# eksos-rj45-breakout-for_slot.net
KiCad netlist of a schematic drawn in EAGLE
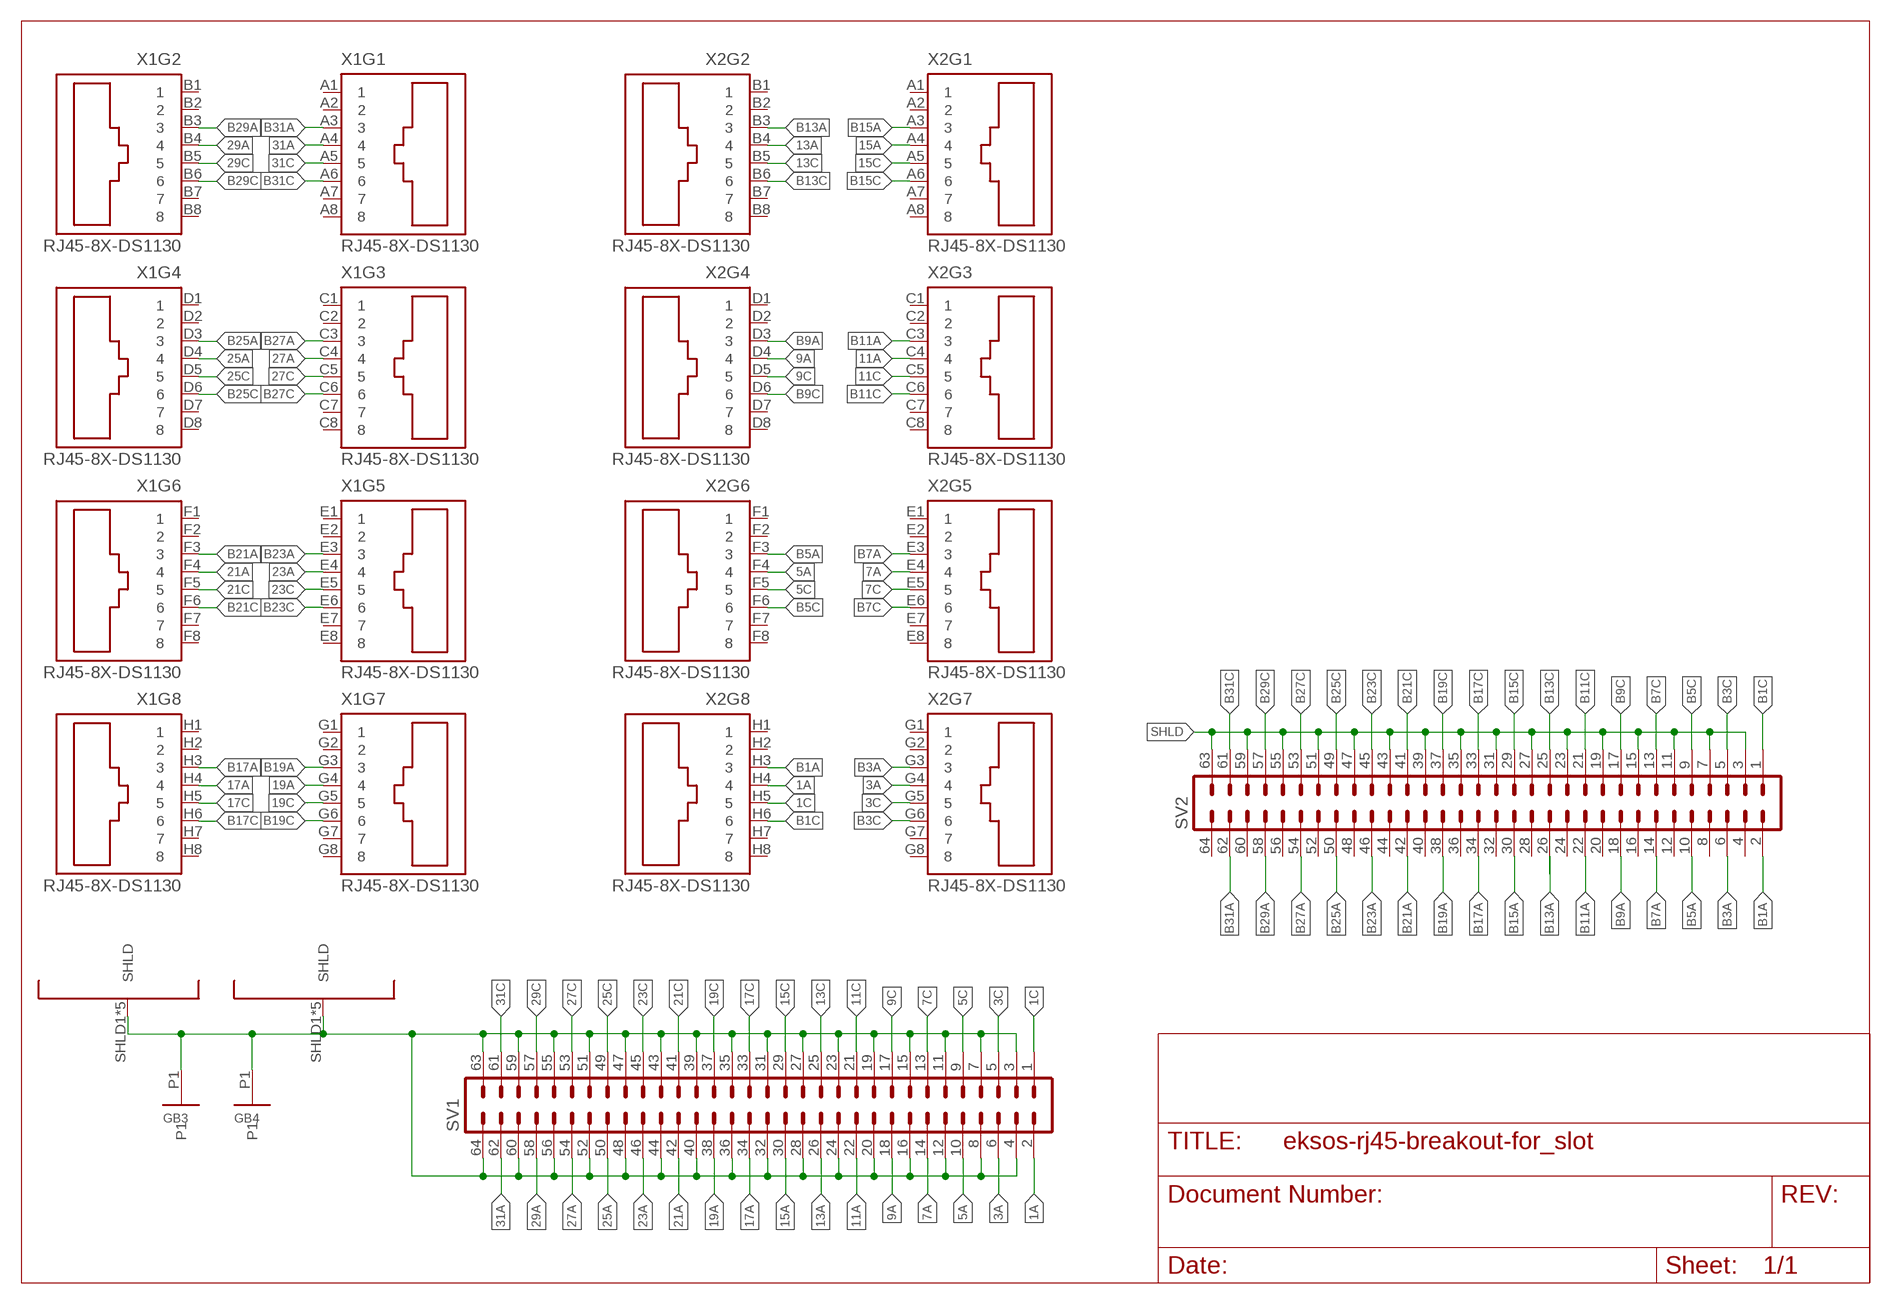
[diagram p0: schematic, sheet 1]

(export (version "E")
  (design (tool "Eeschema 10.0.6"))
  (components
    (comp (ref "GB3")
      (value "GEWINDEBLOCK-6X6X12M3")
      (footprint "eagle-import:GB6X6X12_VIA")
      (libsource (lib "eagle-import") (part "GEWINDEBLOCK-6X6X12M3"))
    )
    (comp (ref "GB4")
      (value "GEWINDEBLOCK-6X6X12M3")
      (footprint "eagle-import:GB6X6X12_VIA")
      (libsource (lib "eagle-import") (part "GEWINDEBLOCK-6X6X12M3"))
    )
    (comp (ref "SV1")
      (value "ML64")
      (footprint "eagle-import:ML64")
      (libsource (lib "eagle-import") (part "ML64"))
    )
    (comp (ref "SV2")
      (value "ML64")
      (footprint "eagle-import:ML64")
      (libsource (lib "eagle-import") (part "ML64"))
    )
    (comp (ref "X1")
      (value "RJ45-8X-DS1130")
      (footprint "eagle-import:DS1130")
      (libsource (lib "eagle-import") (part "RJ45-8X-DS1130"))
    )
    (comp (ref "X2")
      (value "RJ45-8X-DS1130")
      (footprint "eagle-import:DS1130")
      (libsource (lib "eagle-import") (part "RJ45-8X-DS1130"))
    )
  )
  (nets
    (net (code "1") (name "1A") (class "Default")
      (node (ref "SV1") (pin "2") (pinfunction "2_2") (pintype "passive"))
      (node (ref "X2") (pin "H4") (pinfunction "4_H4") (pintype "passive"))
    )
    (net (code "2") (name "1C") (class "Default")
      (node (ref "SV1") (pin "1") (pinfunction "1_1") (pintype "passive"))
      (node (ref "X2") (pin "H5") (pinfunction "5_H5") (pintype "passive"))
    )
    (net (code "3") (name "3A") (class "Default")
      (node (ref "SV1") (pin "6") (pinfunction "6_6") (pintype "passive"))
      (node (ref "X2") (pin "G4") (pinfunction "4_G4") (pintype "passive"))
    )
    (net (code "4") (name "3C") (class "Default")
      (node (ref "SV1") (pin "5") (pinfunction "5_5") (pintype "passive"))
      (node (ref "X2") (pin "G5") (pinfunction "5_G5") (pintype "passive"))
    )
    (net (code "5") (name "5A") (class "Default")
      (node (ref "SV1") (pin "10") (pinfunction "10_10") (pintype "passive"))
      (node (ref "X2") (pin "F4") (pinfunction "4_F4") (pintype "passive"))
    )
    (net (code "6") (name "5C") (class "Default")
      (node (ref "SV1") (pin "9") (pinfunction "9_9") (pintype "passive"))
      (node (ref "X2") (pin "F5") (pinfunction "5_F5") (pintype "passive"))
    )
    (net (code "7") (name "7A") (class "Default")
      (node (ref "SV1") (pin "14") (pinfunction "14_14") (pintype "passive"))
      (node (ref "X2") (pin "E4") (pinfunction "4_E4") (pintype "passive"))
    )
    (net (code "8") (name "7C") (class "Default")
      (node (ref "SV1") (pin "13") (pinfunction "13_13") (pintype "passive"))
      (node (ref "X2") (pin "E5") (pinfunction "5_E5") (pintype "passive"))
    )
    (net (code "9") (name "9A") (class "Default")
      (node (ref "SV1") (pin "18") (pinfunction "18_18") (pintype "passive"))
      (node (ref "X2") (pin "D4") (pinfunction "4_D4") (pintype "passive"))
    )
    (net (code "10") (name "9C") (class "Default")
      (node (ref "SV1") (pin "17") (pinfunction "17_17") (pintype "passive"))
      (node (ref "X2") (pin "D5") (pinfunction "5_D5") (pintype "passive"))
    )
    (net (code "11") (name "11A") (class "Default")
      (node (ref "SV1") (pin "22") (pinfunction "22_22") (pintype "passive"))
      (node (ref "X2") (pin "C4") (pinfunction "4_C4") (pintype "passive"))
    )
    (net (code "12") (name "11C") (class "Default")
      (node (ref "SV1") (pin "21") (pinfunction "21_21") (pintype "passive"))
      (node (ref "X2") (pin "C5") (pinfunction "5_C5") (pintype "passive"))
    )
    (net (code "13") (name "13A") (class "Default")
      (node (ref "SV1") (pin "26") (pinfunction "26_26") (pintype "passive"))
      (node (ref "X2") (pin "B4") (pinfunction "4_B4") (pintype "passive"))
    )
    (net (code "14") (name "13C") (class "Default")
      (node (ref "SV1") (pin "25") (pinfunction "25_25") (pintype "passive"))
      (node (ref "X2") (pin "B5") (pinfunction "5_B5") (pintype "passive"))
    )
    (net (code "15") (name "15A") (class "Default")
      (node (ref "SV1") (pin "30") (pinfunction "30_30") (pintype "passive"))
      (node (ref "X2") (pin "A4") (pinfunction "4_A4") (pintype "passive"))
    )
    (net (code "16") (name "15C") (class "Default")
      (node (ref "SV1") (pin "29") (pinfunction "29_29") (pintype "passive"))
      (node (ref "X2") (pin "A5") (pinfunction "5_A5") (pintype "passive"))
    )
    (net (code "17") (name "17A") (class "Default")
      (node (ref "SV1") (pin "34") (pinfunction "34_34") (pintype "passive"))
      (node (ref "X1") (pin "H4") (pinfunction "4_H4") (pintype "passive"))
    )
    (net (code "18") (name "17C") (class "Default")
      (node (ref "SV1") (pin "33") (pinfunction "33_33") (pintype "passive"))
      (node (ref "X1") (pin "H5") (pinfunction "5_H5") (pintype "passive"))
    )
    (net (code "19") (name "19A") (class "Default")
      (node (ref "SV1") (pin "38") (pinfunction "38_38") (pintype "passive"))
      (node (ref "X1") (pin "G4") (pinfunction "4_G4") (pintype "passive"))
    )
    (net (code "20") (name "19C") (class "Default")
      (node (ref "SV1") (pin "37") (pinfunction "37_37") (pintype "passive"))
      (node (ref "X1") (pin "G5") (pinfunction "5_G5") (pintype "passive"))
    )
    (net (code "21") (name "21A") (class "Default")
      (node (ref "SV1") (pin "42") (pinfunction "42_42") (pintype "passive"))
      (node (ref "X1") (pin "F4") (pinfunction "4_F4") (pintype "passive"))
    )
    (net (code "22") (name "21C") (class "Default")
      (node (ref "SV1") (pin "41") (pinfunction "41_41") (pintype "passive"))
      (node (ref "X1") (pin "F5") (pinfunction "5_F5") (pintype "passive"))
    )
    (net (code "23") (name "23A") (class "Default")
      (node (ref "SV1") (pin "46") (pinfunction "46_46") (pintype "passive"))
      (node (ref "X1") (pin "E4") (pinfunction "4_E4") (pintype "passive"))
    )
    (net (code "24") (name "23C") (class "Default")
      (node (ref "SV1") (pin "45") (pinfunction "45_45") (pintype "passive"))
      (node (ref "X1") (pin "E5") (pinfunction "5_E5") (pintype "passive"))
    )
    (net (code "25") (name "25A") (class "Default")
      (node (ref "SV1") (pin "50") (pinfunction "50_50") (pintype "passive"))
      (node (ref "X1") (pin "D4") (pinfunction "4_D4") (pintype "passive"))
    )
    (net (code "26") (name "25C") (class "Default")
      (node (ref "SV1") (pin "49") (pinfunction "49_49") (pintype "passive"))
      (node (ref "X1") (pin "D5") (pinfunction "5_D5") (pintype "passive"))
    )
    (net (code "27") (name "27A") (class "Default")
      (node (ref "SV1") (pin "54") (pinfunction "54_54") (pintype "passive"))
      (node (ref "X1") (pin "C4") (pinfunction "4_C4") (pintype "passive"))
    )
    (net (code "28") (name "27C") (class "Default")
      (node (ref "SV1") (pin "53") (pinfunction "53_53") (pintype "passive"))
      (node (ref "X1") (pin "C5") (pinfunction "5_C5") (pintype "passive"))
    )
    (net (code "29") (name "29A") (class "Default")
      (node (ref "SV1") (pin "58") (pinfunction "58_58") (pintype "passive"))
      (node (ref "X1") (pin "B4") (pinfunction "4_B4") (pintype "passive"))
    )
    (net (code "30") (name "29C") (class "Default")
      (node (ref "SV1") (pin "57") (pinfunction "57_57") (pintype "passive"))
      (node (ref "X1") (pin "B5") (pinfunction "5_B5") (pintype "passive"))
    )
    (net (code "31") (name "31A") (class "Default")
      (node (ref "SV1") (pin "62") (pinfunction "62_62") (pintype "passive"))
      (node (ref "X1") (pin "A4") (pinfunction "4_A4") (pintype "passive"))
    )
    (net (code "32") (name "31C") (class "Default")
      (node (ref "SV1") (pin "61") (pinfunction "61_61") (pintype "passive"))
      (node (ref "X1") (pin "A5") (pinfunction "5_A5") (pintype "passive"))
    )
    (net (code "33") (name "B1A") (class "Default")
      (node (ref "SV2") (pin "2") (pinfunction "2_2") (pintype "passive"))
      (node (ref "X2") (pin "H3") (pinfunction "3_H3") (pintype "passive"))
    )
    (net (code "34") (name "B1C") (class "Default")
      (node (ref "SV2") (pin "1") (pinfunction "1_1") (pintype "passive"))
      (node (ref "X2") (pin "H6") (pinfunction "6_H6") (pintype "passive"))
    )
    (net (code "35") (name "B3A") (class "Default")
      (node (ref "SV2") (pin "6") (pinfunction "6_6") (pintype "passive"))
      (node (ref "X2") (pin "G3") (pinfunction "3_G3") (pintype "passive"))
    )
    (net (code "36") (name "B3C") (class "Default")
      (node (ref "SV2") (pin "5") (pinfunction "5_5") (pintype "passive"))
      (node (ref "X2") (pin "G6") (pinfunction "6_G6") (pintype "passive"))
    )
    (net (code "37") (name "B5A") (class "Default")
      (node (ref "SV2") (pin "10") (pinfunction "10_10") (pintype "passive"))
      (node (ref "X2") (pin "F3") (pinfunction "3_F3") (pintype "passive"))
    )
    (net (code "38") (name "B5C") (class "Default")
      (node (ref "SV2") (pin "9") (pinfunction "9_9") (pintype "passive"))
      (node (ref "X2") (pin "F6") (pinfunction "6_F6") (pintype "passive"))
    )
    (net (code "39") (name "B7A") (class "Default")
      (node (ref "SV2") (pin "14") (pinfunction "14_14") (pintype "passive"))
      (node (ref "X2") (pin "E3") (pinfunction "3_E3") (pintype "passive"))
    )
    (net (code "40") (name "B7C") (class "Default")
      (node (ref "SV2") (pin "13") (pinfunction "13_13") (pintype "passive"))
      (node (ref "X2") (pin "E6") (pinfunction "6_E6") (pintype "passive"))
    )
    (net (code "41") (name "B9A") (class "Default")
      (node (ref "SV2") (pin "18") (pinfunction "18_18") (pintype "passive"))
      (node (ref "X2") (pin "D3") (pinfunction "3_D3") (pintype "passive"))
    )
    (net (code "42") (name "B9C") (class "Default")
      (node (ref "SV2") (pin "17") (pinfunction "17_17") (pintype "passive"))
      (node (ref "X2") (pin "D6") (pinfunction "6_D6") (pintype "passive"))
    )
    (net (code "43") (name "B11A") (class "Default")
      (node (ref "SV2") (pin "22") (pinfunction "22_22") (pintype "passive"))
      (node (ref "X2") (pin "C3") (pinfunction "3_C3") (pintype "passive"))
    )
    (net (code "44") (name "B11C") (class "Default")
      (node (ref "SV2") (pin "21") (pinfunction "21_21") (pintype "passive"))
      (node (ref "X2") (pin "C6") (pinfunction "6_C6") (pintype "passive"))
    )
    (net (code "45") (name "B13A") (class "Default")
      (node (ref "SV2") (pin "26") (pinfunction "26_26") (pintype "passive"))
      (node (ref "X2") (pin "B3") (pinfunction "3_B3") (pintype "passive"))
    )
    (net (code "46") (name "B13C") (class "Default")
      (node (ref "SV2") (pin "25") (pinfunction "25_25") (pintype "passive"))
      (node (ref "X2") (pin "B6") (pinfunction "6_B6") (pintype "passive"))
    )
    (net (code "47") (name "B15A") (class "Default")
      (node (ref "SV2") (pin "30") (pinfunction "30_30") (pintype "passive"))
      (node (ref "X2") (pin "A3") (pinfunction "3_A3") (pintype "passive"))
    )
    (net (code "48") (name "B15C") (class "Default")
      (node (ref "SV2") (pin "29") (pinfunction "29_29") (pintype "passive"))
      (node (ref "X2") (pin "A6") (pinfunction "6_A6") (pintype "passive"))
    )
    (net (code "49") (name "B17A") (class "Default")
      (node (ref "SV2") (pin "34") (pinfunction "34_34") (pintype "passive"))
      (node (ref "X1") (pin "H3") (pinfunction "3_H3") (pintype "passive"))
    )
    (net (code "50") (name "B17C") (class "Default")
      (node (ref "SV2") (pin "33") (pinfunction "33_33") (pintype "passive"))
      (node (ref "X1") (pin "H6") (pinfunction "6_H6") (pintype "passive"))
    )
    (net (code "51") (name "B19A") (class "Default")
      (node (ref "SV2") (pin "38") (pinfunction "38_38") (pintype "passive"))
      (node (ref "X1") (pin "G3") (pinfunction "3_G3") (pintype "passive"))
    )
    (net (code "52") (name "B19C") (class "Default")
      (node (ref "SV2") (pin "37") (pinfunction "37_37") (pintype "passive"))
      (node (ref "X1") (pin "G6") (pinfunction "6_G6") (pintype "passive"))
    )
    (net (code "53") (name "B21A") (class "Default")
      (node (ref "SV2") (pin "42") (pinfunction "42_42") (pintype "passive"))
      (node (ref "X1") (pin "F3") (pinfunction "3_F3") (pintype "passive"))
    )
    (net (code "54") (name "B21C") (class "Default")
      (node (ref "SV2") (pin "41") (pinfunction "41_41") (pintype "passive"))
      (node (ref "X1") (pin "F6") (pinfunction "6_F6") (pintype "passive"))
    )
    (net (code "55") (name "B23A") (class "Default")
      (node (ref "SV2") (pin "46") (pinfunction "46_46") (pintype "passive"))
      (node (ref "X1") (pin "E3") (pinfunction "3_E3") (pintype "passive"))
    )
    (net (code "56") (name "B23C") (class "Default")
      (node (ref "SV2") (pin "45") (pinfunction "45_45") (pintype "passive"))
      (node (ref "X1") (pin "E6") (pinfunction "6_E6") (pintype "passive"))
    )
    (net (code "57") (name "B25A") (class "Default")
      (node (ref "SV2") (pin "50") (pinfunction "50_50") (pintype "passive"))
      (node (ref "X1") (pin "D3") (pinfunction "3_D3") (pintype "passive"))
    )
    (net (code "58") (name "B25C") (class "Default")
      (node (ref "SV2") (pin "49") (pinfunction "49_49") (pintype "passive"))
      (node (ref "X1") (pin "D6") (pinfunction "6_D6") (pintype "passive"))
    )
    (net (code "59") (name "B27A") (class "Default")
      (node (ref "SV2") (pin "54") (pinfunction "54_54") (pintype "passive"))
      (node (ref "X1") (pin "C3") (pinfunction "3_C3") (pintype "passive"))
    )
    (net (code "60") (name "B27C") (class "Default")
      (node (ref "SV2") (pin "53") (pinfunction "53_53") (pintype "passive"))
      (node (ref "X1") (pin "C6") (pinfunction "6_C6") (pintype "passive"))
    )
    (net (code "61") (name "B29A") (class "Default")
      (node (ref "SV2") (pin "58") (pinfunction "58_58") (pintype "passive"))
      (node (ref "X1") (pin "B3") (pinfunction "3_B3") (pintype "passive"))
    )
    (net (code "62") (name "B29C") (class "Default")
      (node (ref "SV2") (pin "57") (pinfunction "57_57") (pintype "passive"))
      (node (ref "X1") (pin "B6") (pinfunction "6_B6") (pintype "passive"))
    )
    (net (code "63") (name "B31A") (class "Default")
      (node (ref "SV2") (pin "62") (pinfunction "62_62") (pintype "passive"))
      (node (ref "X1") (pin "A3") (pinfunction "3_A3") (pintype "passive"))
    )
    (net (code "64") (name "B31C") (class "Default")
      (node (ref "SV2") (pin "61") (pinfunction "61_61") (pintype "passive"))
      (node (ref "X1") (pin "A6") (pinfunction "6_A6") (pintype "passive"))
    )
    (net (code "65") (name "SHLD") (class "Default")
      (node (ref "GB3") (pin "P1") (pinfunction "P1_P1") (pintype "bidirectional"))
      (node (ref "GB4") (pin "P1") (pinfunction "P1_P1") (pintype "bidirectional"))
      (node (ref "SV1") (pin "11") (pinfunction "11_11") (pintype "passive"))
      (node (ref "SV1") (pin "12") (pinfunction "12_12") (pintype "passive"))
      (node (ref "SV1") (pin "15") (pinfunction "15_15") (pintype "passive"))
      (node (ref "SV1") (pin "16") (pinfunction "16_16") (pintype "passive"))
      (node (ref "SV1") (pin "19") (pinfunction "19_19") (pintype "passive"))
      (node (ref "SV1") (pin "20") (pinfunction "20_20") (pintype "passive"))
      (node (ref "SV1") (pin "23") (pinfunction "23_23") (pintype "passive"))
      (node (ref "SV1") (pin "24") (pinfunction "24_24") (pintype "passive"))
      (node (ref "SV1") (pin "27") (pinfunction "27_27") (pintype "passive"))
      (node (ref "SV1") (pin "28") (pinfunction "28_28") (pintype "passive"))
      (node (ref "SV1") (pin "3") (pinfunction "3_3") (pintype "passive"))
      (node (ref "SV1") (pin "31") (pinfunction "31_31") (pintype "passive"))
      (node (ref "SV1") (pin "32") (pinfunction "32_32") (pintype "passive"))
      (node (ref "SV1") (pin "35") (pinfunction "35_35") (pintype "passive"))
      (node (ref "SV1") (pin "36") (pinfunction "36_36") (pintype "passive"))
      (node (ref "SV1") (pin "39") (pinfunction "39_39") (pintype "passive"))
      (node (ref "SV1") (pin "4") (pinfunction "4_4") (pintype "passive"))
      (node (ref "SV1") (pin "40") (pinfunction "40_40") (pintype "passive"))
      (node (ref "SV1") (pin "43") (pinfunction "43_43") (pintype "passive"))
      (node (ref "SV1") (pin "44") (pinfunction "44_44") (pintype "passive"))
      (node (ref "SV1") (pin "47") (pinfunction "47_47") (pintype "passive"))
      (node (ref "SV1") (pin "48") (pinfunction "48_48") (pintype "passive"))
      (node (ref "SV1") (pin "51") (pinfunction "51_51") (pintype "passive"))
      (node (ref "SV1") (pin "52") (pinfunction "52_52") (pintype "passive"))
      (node (ref "SV1") (pin "55") (pinfunction "55_55") (pintype "passive"))
      (node (ref "SV1") (pin "56") (pinfunction "56_56") (pintype "passive"))
      (node (ref "SV1") (pin "59") (pinfunction "59_59") (pintype "passive"))
      (node (ref "SV1") (pin "60") (pinfunction "60_60") (pintype "passive"))
      (node (ref "SV1") (pin "63") (pinfunction "63_63") (pintype "passive"))
      (node (ref "SV1") (pin "64") (pinfunction "64_64") (pintype "passive"))
      (node (ref "SV1") (pin "7") (pinfunction "7_7") (pintype "passive"))
      (node (ref "SV1") (pin "8") (pinfunction "8_8") (pintype "passive"))
      (node (ref "SV2") (pin "11") (pinfunction "11_11") (pintype "passive"))
      (node (ref "SV2") (pin "15") (pinfunction "15_15") (pintype "passive"))
      (node (ref "SV2") (pin "19") (pinfunction "19_19") (pintype "passive"))
      (node (ref "SV2") (pin "23") (pinfunction "23_23") (pintype "passive"))
      (node (ref "SV2") (pin "27") (pinfunction "27_27") (pintype "passive"))
      (node (ref "SV2") (pin "3") (pinfunction "3_3") (pintype "passive"))
      (node (ref "SV2") (pin "31") (pinfunction "31_31") (pintype "passive"))
      (node (ref "SV2") (pin "35") (pinfunction "35_35") (pintype "passive"))
      (node (ref "SV2") (pin "39") (pinfunction "39_39") (pintype "passive"))
      (node (ref "SV2") (pin "43") (pinfunction "43_43") (pintype "passive"))
      (node (ref "SV2") (pin "47") (pinfunction "47_47") (pintype "passive"))
      (node (ref "SV2") (pin "51") (pinfunction "51_51") (pintype "passive"))
      (node (ref "SV2") (pin "55") (pinfunction "55_55") (pintype "passive"))
      (node (ref "SV2") (pin "59") (pinfunction "59_59") (pintype "passive"))
      (node (ref "SV2") (pin "63") (pinfunction "63_63") (pintype "passive"))
      (node (ref "SV2") (pin "7") (pinfunction "7_7") (pintype "passive"))
      (node (ref "X1") (pin "SHLD1") (pinfunction "SHLD_SHLD1") (pintype "bidirectional"))
      (node (ref "X1") (pin "SHLD2") (pinfunction "SHLD_SHLD2") (pintype "bidirectional"))
      (node (ref "X1") (pin "SHLD3") (pinfunction "SHLD_SHLD3") (pintype "bidirectional"))
      (node (ref "X1") (pin "SHLD4") (pinfunction "SHLD_SHLD4") (pintype "bidirectional"))
      (node (ref "X1") (pin "SHLD5") (pinfunction "SHLD_SHLD5") (pintype "bidirectional"))
      (node (ref "X2") (pin "SHLD1") (pinfunction "SHLD_SHLD1") (pintype "bidirectional"))
      (node (ref "X2") (pin "SHLD2") (pinfunction "SHLD_SHLD2") (pintype "bidirectional"))
      (node (ref "X2") (pin "SHLD3") (pinfunction "SHLD_SHLD3") (pintype "bidirectional"))
      (node (ref "X2") (pin "SHLD4") (pinfunction "SHLD_SHLD4") (pintype "bidirectional"))
      (node (ref "X2") (pin "SHLD5") (pinfunction "SHLD_SHLD5") (pintype "bidirectional"))
    )
    (net (code "66") (name "unconnected-(SV2-Pad4)") (class "Default")
      (node (ref "SV2") (pin "4") (pinfunction "4_4") (pintype "passive"))
    )
    (net (code "67") (name "unconnected-(SV2-Pad8)") (class "Default")
      (node (ref "SV2") (pin "8") (pinfunction "8_8") (pintype "passive"))
    )
    (net (code "68") (name "unconnected-(SV2-Pad12)") (class "Default")
      (node (ref "SV2") (pin "12") (pinfunction "12_12") (pintype "passive"))
    )
    (net (code "69") (name "unconnected-(SV2-Pad16)") (class "Default")
      (node (ref "SV2") (pin "16") (pinfunction "16_16") (pintype "passive"))
    )
    (net (code "70") (name "unconnected-(SV2-Pad20)") (class "Default")
      (node (ref "SV2") (pin "20") (pinfunction "20_20") (pintype "passive"))
    )
    (net (code "71") (name "unconnected-(SV2-Pad24)") (class "Default")
      (node (ref "SV2") (pin "24") (pinfunction "24_24") (pintype "passive"))
    )
    (net (code "72") (name "unconnected-(SV2-Pad28)") (class "Default")
      (node (ref "SV2") (pin "28") (pinfunction "28_28") (pintype "passive"))
    )
    (net (code "73") (name "unconnected-(SV2-Pad32)") (class "Default")
      (node (ref "SV2") (pin "32") (pinfunction "32_32") (pintype "passive"))
    )
    (net (code "74") (name "unconnected-(SV2-Pad36)") (class "Default")
      (node (ref "SV2") (pin "36") (pinfunction "36_36") (pintype "passive"))
    )
    (net (code "75") (name "unconnected-(SV2-Pad40)") (class "Default")
      (node (ref "SV2") (pin "40") (pinfunction "40_40") (pintype "passive"))
    )
    (net (code "76") (name "unconnected-(SV2-Pad44)") (class "Default")
      (node (ref "SV2") (pin "44") (pinfunction "44_44") (pintype "passive"))
    )
    (net (code "77") (name "unconnected-(SV2-Pad48)") (class "Default")
      (node (ref "SV2") (pin "48") (pinfunction "48_48") (pintype "passive"))
    )
    (net (code "78") (name "unconnected-(SV2-Pad52)") (class "Default")
      (node (ref "SV2") (pin "52") (pinfunction "52_52") (pintype "passive"))
    )
    (net (code "79") (name "unconnected-(SV2-Pad56)") (class "Default")
      (node (ref "SV2") (pin "56") (pinfunction "56_56") (pintype "passive"))
    )
    (net (code "80") (name "unconnected-(SV2-Pad60)") (class "Default")
      (node (ref "SV2") (pin "60") (pinfunction "60_60") (pintype "passive"))
    )
    (net (code "81") (name "unconnected-(SV2-Pad64)") (class "Default")
      (node (ref "SV2") (pin "64") (pinfunction "64_64") (pintype "passive"))
    )
    (net (code "82") (name "unconnected-(X1B-1-PadA1)") (class "Default")
      (node (ref "X1") (pin "A1") (pinfunction "1_A1") (pintype "passive"))
    )
    (net (code "83") (name "unconnected-(X1B-2-PadA2)") (class "Default")
      (node (ref "X1") (pin "A2") (pinfunction "2_A2") (pintype "passive"))
    )
    (net (code "84") (name "unconnected-(X1B-7-PadA7)") (class "Default")
      (node (ref "X1") (pin "A7") (pinfunction "7_A7") (pintype "passive"))
    )
    (net (code "85") (name "unconnected-(X1B-8-PadA8)") (class "Default")
      (node (ref "X1") (pin "A8") (pinfunction "8_A8") (pintype "passive"))
    )
    (net (code "86") (name "unconnected-(X1C-1-PadB1)") (class "Default")
      (node (ref "X1") (pin "B1") (pinfunction "1_B1") (pintype "passive"))
    )
    (net (code "87") (name "unconnected-(X1C-2-PadB2)") (class "Default")
      (node (ref "X1") (pin "B2") (pinfunction "2_B2") (pintype "passive"))
    )
    (net (code "88") (name "unconnected-(X1C-7-PadB7)") (class "Default")
      (node (ref "X1") (pin "B7") (pinfunction "7_B7") (pintype "passive"))
    )
    (net (code "89") (name "unconnected-(X1C-8-PadB8)") (class "Default")
      (node (ref "X1") (pin "B8") (pinfunction "8_B8") (pintype "passive"))
    )
    (net (code "90") (name "unconnected-(X1D-1-PadC1)") (class "Default")
      (node (ref "X1") (pin "C1") (pinfunction "1_C1") (pintype "passive"))
    )
    (net (code "91") (name "unconnected-(X1D-2-PadC2)") (class "Default")
      (node (ref "X1") (pin "C2") (pinfunction "2_C2") (pintype "passive"))
    )
    (net (code "92") (name "unconnected-(X1D-7-PadC7)") (class "Default")
      (node (ref "X1") (pin "C7") (pinfunction "7_C7") (pintype "passive"))
    )
    (net (code "93") (name "unconnected-(X1D-8-PadC8)") (class "Default")
      (node (ref "X1") (pin "C8") (pinfunction "8_C8") (pintype "passive"))
    )
    (net (code "94") (name "unconnected-(X1E-1-PadD1)") (class "Default")
      (node (ref "X1") (pin "D1") (pinfunction "1_D1") (pintype "passive"))
    )
    (net (code "95") (name "unconnected-(X1E-2-PadD2)") (class "Default")
      (node (ref "X1") (pin "D2") (pinfunction "2_D2") (pintype "passive"))
    )
    (net (code "96") (name "unconnected-(X1E-7-PadD7)") (class "Default")
      (node (ref "X1") (pin "D7") (pinfunction "7_D7") (pintype "passive"))
    )
    (net (code "97") (name "unconnected-(X1E-8-PadD8)") (class "Default")
      (node (ref "X1") (pin "D8") (pinfunction "8_D8") (pintype "passive"))
    )
    (net (code "98") (name "unconnected-(X1F-1-PadE1)") (class "Default")
      (node (ref "X1") (pin "E1") (pinfunction "1_E1") (pintype "passive"))
    )
    (net (code "99") (name "unconnected-(X1F-2-PadE2)") (class "Default")
      (node (ref "X1") (pin "E2") (pinfunction "2_E2") (pintype "passive"))
    )
    (net (code "100") (name "unconnected-(X1F-7-PadE7)") (class "Default")
      (node (ref "X1") (pin "E7") (pinfunction "7_E7") (pintype "passive"))
    )
    (net (code "101") (name "unconnected-(X1F-8-PadE8)") (class "Default")
      (node (ref "X1") (pin "E8") (pinfunction "8_E8") (pintype "passive"))
    )
    (net (code "102") (name "unconnected-(X1G-1-PadF1)") (class "Default")
      (node (ref "X1") (pin "F1") (pinfunction "1_F1") (pintype "passive"))
    )
    (net (code "103") (name "unconnected-(X1G-2-PadF2)") (class "Default")
      (node (ref "X1") (pin "F2") (pinfunction "2_F2") (pintype "passive"))
    )
    (net (code "104") (name "unconnected-(X1G-7-PadF7)") (class "Default")
      (node (ref "X1") (pin "F7") (pinfunction "7_F7") (pintype "passive"))
    )
    (net (code "105") (name "unconnected-(X1G-8-PadF8)") (class "Default")
      (node (ref "X1") (pin "F8") (pinfunction "8_F8") (pintype "passive"))
    )
    (net (code "106") (name "unconnected-(X1H-1-PadG1)") (class "Default")
      (node (ref "X1") (pin "G1") (pinfunction "1_G1") (pintype "passive"))
    )
    (net (code "107") (name "unconnected-(X1H-2-PadG2)") (class "Default")
      (node (ref "X1") (pin "G2") (pinfunction "2_G2") (pintype "passive"))
    )
    (net (code "108") (name "unconnected-(X1H-7-PadG7)") (class "Default")
      (node (ref "X1") (pin "G7") (pinfunction "7_G7") (pintype "passive"))
    )
    (net (code "109") (name "unconnected-(X1H-8-PadG8)") (class "Default")
      (node (ref "X1") (pin "G8") (pinfunction "8_G8") (pintype "passive"))
    )
    (net (code "110") (name "unconnected-(X1I-1-PadH1)") (class "Default")
      (node (ref "X1") (pin "H1") (pinfunction "1_H1") (pintype "passive"))
    )
    (net (code "111") (name "unconnected-(X1I-2-PadH2)") (class "Default")
      (node (ref "X1") (pin "H2") (pinfunction "2_H2") (pintype "passive"))
    )
    (net (code "112") (name "unconnected-(X1I-7-PadH7)") (class "Default")
      (node (ref "X1") (pin "H7") (pinfunction "7_H7") (pintype "passive"))
    )
    (net (code "113") (name "unconnected-(X1I-8-PadH8)") (class "Default")
      (node (ref "X1") (pin "H8") (pinfunction "8_H8") (pintype "passive"))
    )
    (net (code "114") (name "unconnected-(X2B-1-PadA1)") (class "Default")
      (node (ref "X2") (pin "A1") (pinfunction "1_A1") (pintype "passive"))
    )
    (net (code "115") (name "unconnected-(X2B-2-PadA2)") (class "Default")
      (node (ref "X2") (pin "A2") (pinfunction "2_A2") (pintype "passive"))
    )
    (net (code "116") (name "unconnected-(X2B-7-PadA7)") (class "Default")
      (node (ref "X2") (pin "A7") (pinfunction "7_A7") (pintype "passive"))
    )
    (net (code "117") (name "unconnected-(X2B-8-PadA8)") (class "Default")
      (node (ref "X2") (pin "A8") (pinfunction "8_A8") (pintype "passive"))
    )
    (net (code "118") (name "unconnected-(X2C-1-PadB1)") (class "Default")
      (node (ref "X2") (pin "B1") (pinfunction "1_B1") (pintype "passive"))
    )
    (net (code "119") (name "unconnected-(X2C-2-PadB2)") (class "Default")
      (node (ref "X2") (pin "B2") (pinfunction "2_B2") (pintype "passive"))
    )
    (net (code "120") (name "unconnected-(X2C-7-PadB7)") (class "Default")
      (node (ref "X2") (pin "B7") (pinfunction "7_B7") (pintype "passive"))
    )
    (net (code "121") (name "unconnected-(X2C-8-PadB8)") (class "Default")
      (node (ref "X2") (pin "B8") (pinfunction "8_B8") (pintype "passive"))
    )
    (net (code "122") (name "unconnected-(X2D-1-PadC1)") (class "Default")
      (node (ref "X2") (pin "C1") (pinfunction "1_C1") (pintype "passive"))
    )
    (net (code "123") (name "unconnected-(X2D-2-PadC2)") (class "Default")
      (node (ref "X2") (pin "C2") (pinfunction "2_C2") (pintype "passive"))
    )
    (net (code "124") (name "unconnected-(X2D-7-PadC7)") (class "Default")
      (node (ref "X2") (pin "C7") (pinfunction "7_C7") (pintype "passive"))
    )
    (net (code "125") (name "unconnected-(X2D-8-PadC8)") (class "Default")
      (node (ref "X2") (pin "C8") (pinfunction "8_C8") (pintype "passive"))
    )
    (net (code "126") (name "unconnected-(X2E-1-PadD1)") (class "Default")
      (node (ref "X2") (pin "D1") (pinfunction "1_D1") (pintype "passive"))
    )
    (net (code "127") (name "unconnected-(X2E-2-PadD2)") (class "Default")
      (node (ref "X2") (pin "D2") (pinfunction "2_D2") (pintype "passive"))
    )
    (net (code "128") (name "unconnected-(X2E-7-PadD7)") (class "Default")
      (node (ref "X2") (pin "D7") (pinfunction "7_D7") (pintype "passive"))
    )
    (net (code "129") (name "unconnected-(X2E-8-PadD8)") (class "Default")
      (node (ref "X2") (pin "D8") (pinfunction "8_D8") (pintype "passive"))
    )
    (net (code "130") (name "unconnected-(X2F-1-PadE1)") (class "Default")
      (node (ref "X2") (pin "E1") (pinfunction "1_E1") (pintype "passive"))
    )
    (net (code "131") (name "unconnected-(X2F-2-PadE2)") (class "Default")
      (node (ref "X2") (pin "E2") (pinfunction "2_E2") (pintype "passive"))
    )
    (net (code "132") (name "unconnected-(X2F-7-PadE7)") (class "Default")
      (node (ref "X2") (pin "E7") (pinfunction "7_E7") (pintype "passive"))
    )
    (net (code "133") (name "unconnected-(X2F-8-PadE8)") (class "Default")
      (node (ref "X2") (pin "E8") (pinfunction "8_E8") (pintype "passive"))
    )
    (net (code "134") (name "unconnected-(X2G-1-PadF1)") (class "Default")
      (node (ref "X2") (pin "F1") (pinfunction "1_F1") (pintype "passive"))
    )
    (net (code "135") (name "unconnected-(X2G-2-PadF2)") (class "Default")
      (node (ref "X2") (pin "F2") (pinfunction "2_F2") (pintype "passive"))
    )
    (net (code "136") (name "unconnected-(X2G-7-PadF7)") (class "Default")
      (node (ref "X2") (pin "F7") (pinfunction "7_F7") (pintype "passive"))
    )
    (net (code "137") (name "unconnected-(X2G-8-PadF8)") (class "Default")
      (node (ref "X2") (pin "F8") (pinfunction "8_F8") (pintype "passive"))
    )
    (net (code "138") (name "unconnected-(X2H-1-PadG1)") (class "Default")
      (node (ref "X2") (pin "G1") (pinfunction "1_G1") (pintype "passive"))
    )
    (net (code "139") (name "unconnected-(X2H-2-PadG2)") (class "Default")
      (node (ref "X2") (pin "G2") (pinfunction "2_G2") (pintype "passive"))
    )
    (net (code "140") (name "unconnected-(X2H-7-PadG7)") (class "Default")
      (node (ref "X2") (pin "G7") (pinfunction "7_G7") (pintype "passive"))
    )
    (net (code "141") (name "unconnected-(X2H-8-PadG8)") (class "Default")
      (node (ref "X2") (pin "G8") (pinfunction "8_G8") (pintype "passive"))
    )
    (net (code "142") (name "unconnected-(X2I-1-PadH1)") (class "Default")
      (node (ref "X2") (pin "H1") (pinfunction "1_H1") (pintype "passive"))
    )
    (net (code "143") (name "unconnected-(X2I-2-PadH2)") (class "Default")
      (node (ref "X2") (pin "H2") (pinfunction "2_H2") (pintype "passive"))
    )
    (net (code "144") (name "unconnected-(X2I-7-PadH7)") (class "Default")
      (node (ref "X2") (pin "H7") (pinfunction "7_H7") (pintype "passive"))
    )
    (net (code "145") (name "unconnected-(X2I-8-PadH8)") (class "Default")
      (node (ref "X2") (pin "H8") (pinfunction "8_H8") (pintype "passive"))
    )
  )
)
